# Supply_0.net
KiCad netlist of a schematic drawn in Altium Designer
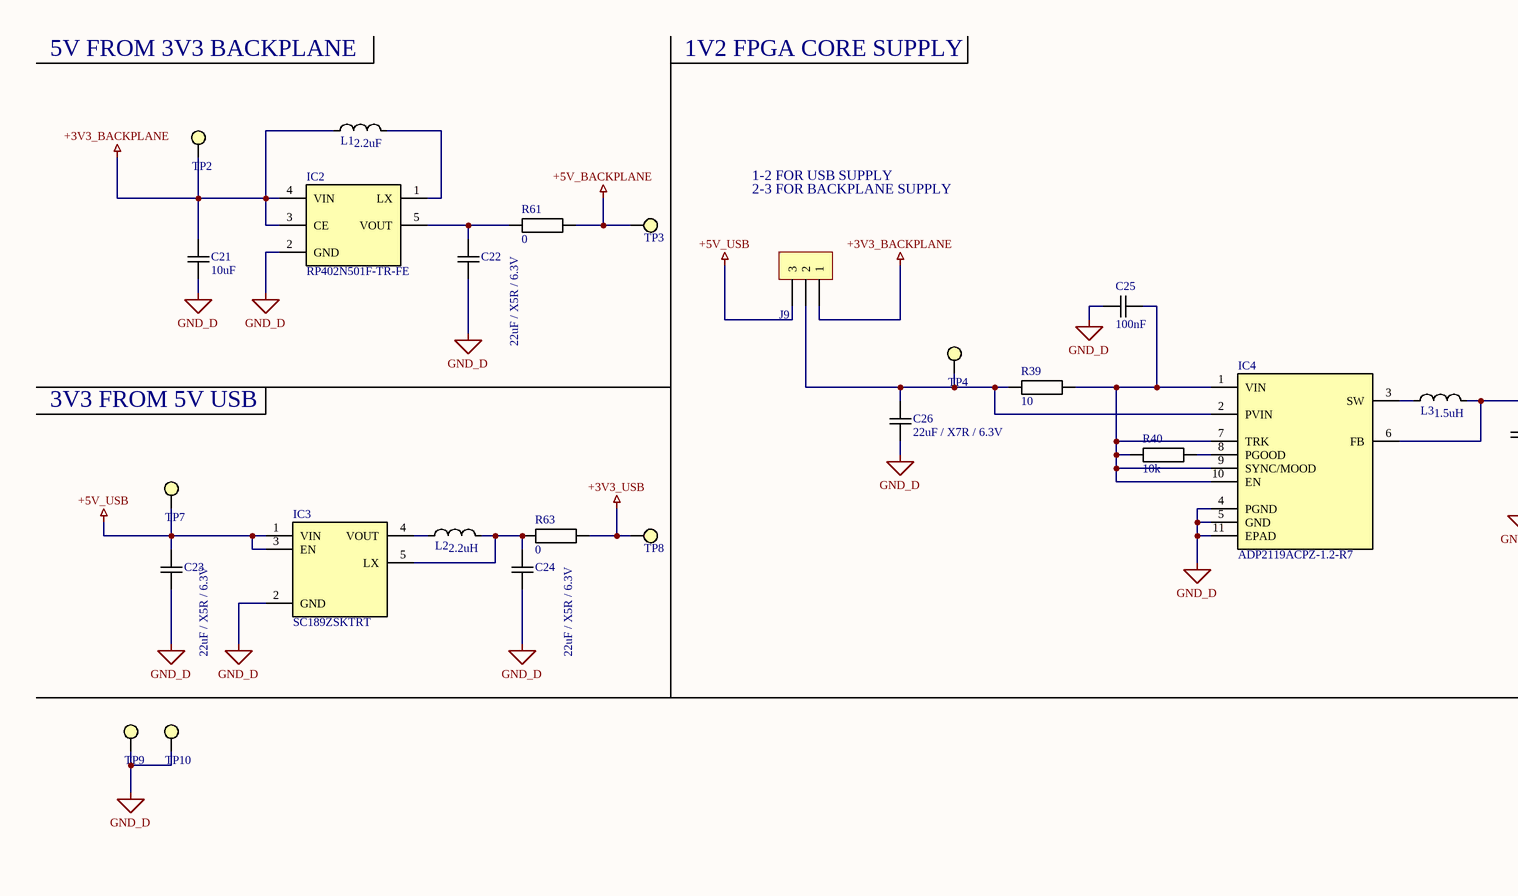
[diagram p0: Supply_0.SchDoc, left]
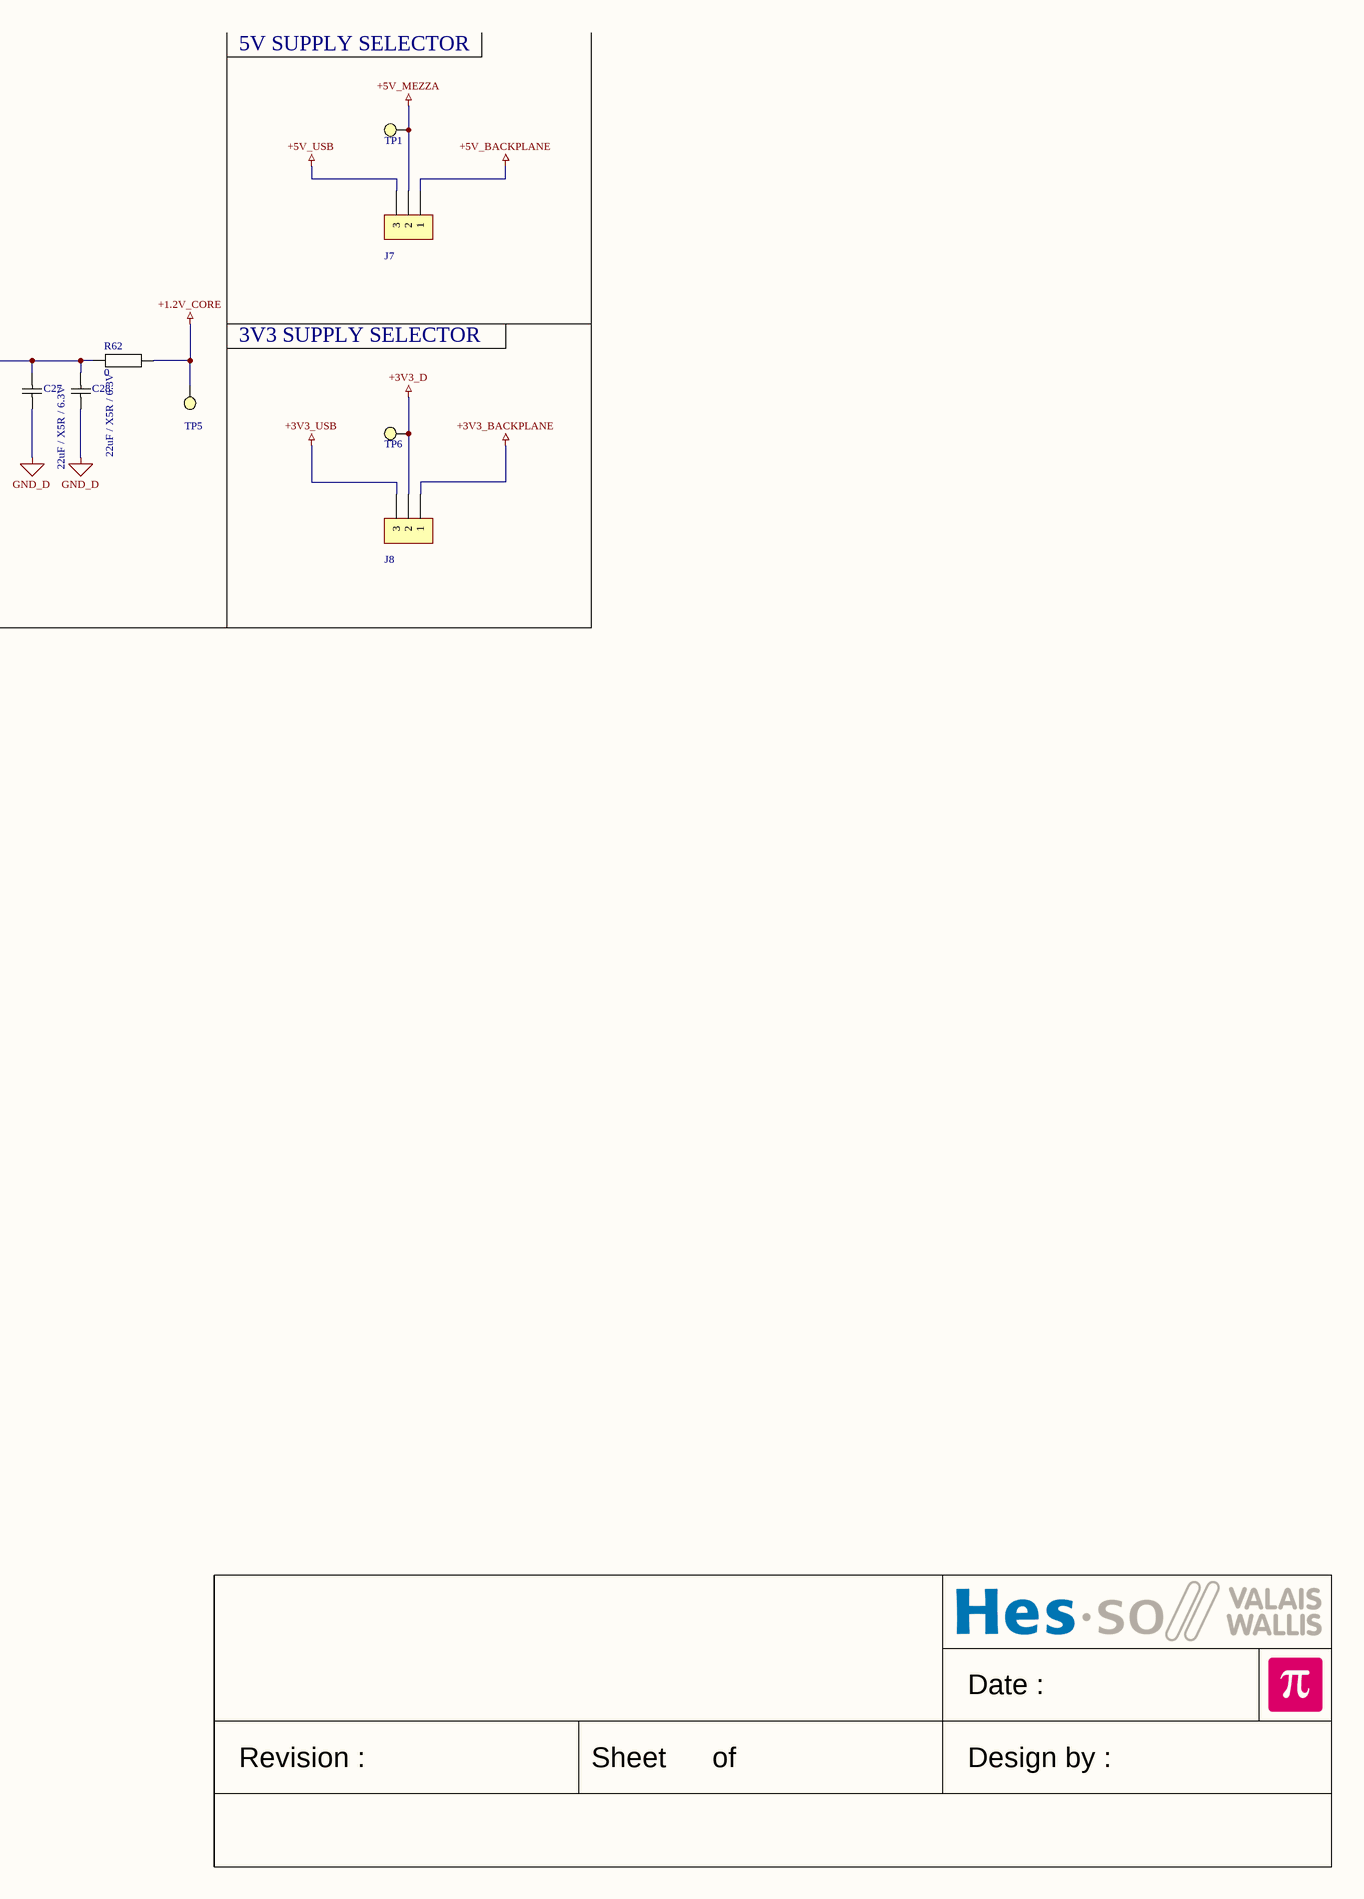
[diagram p1: Supply_0.SchDoc, right]

(export (version "E")
  (design (tool "Eeschema 10.0.6"))
  (components
    (comp (ref "C21")
      (value "10uF")
      (footprint "CAPACITOR 2012 REFLOW")
      (description "Capacitor")
      (libsource (lib "Capacitor") (part "Capacitor"))
    )
    (comp (ref "C22")
      (value "22uF / X5R / 6.3V")
      (footprint "CAPACITOR 2012 REFLOW")
      (description "Capacitor")
      (libsource (lib "Capacitor") (part "Capacitor"))
    )
    (comp (ref "C23")
      (value "22uF / X5R / 6.3V")
      (footprint "CAPACITOR 2012 REFLOW")
      (description "Capacitor")
      (libsource (lib "Capacitor") (part "Capacitor"))
    )
    (comp (ref "C24")
      (value "22uF / X5R / 6.3V")
      (footprint "CAPACITOR 2012 REFLOW")
      (description "Capacitor")
      (libsource (lib "Capacitor") (part "Capacitor"))
    )
    (comp (ref "C25")
      (value "100nF")
      (footprint "CAPACITOR 1608 REFLOW")
      (description "Capacitor")
      (libsource (lib "Capacitor") (part "Capacitor"))
    )
    (comp (ref "C26")
      (value "22uF / X7R / 6.3V")
      (footprint "CAPACITOR 2012 REFLOW")
      (description "Capacitor")
      (libsource (lib "Capacitor") (part "Capacitor"))
    )
    (comp (ref "C27")
      (value "22uF / X5R / 6.3V")
      (footprint "CAPACITOR 2012 REFLOW")
      (description "Capacitor")
      (libsource (lib "Capacitor") (part "Capacitor"))
    )
    (comp (ref "C28")
      (value "22uF / X5R / 6.3V")
      (footprint "CAPACITOR 2012 REFLOW")
      (description "Capacitor")
      (libsource (lib "Capacitor") (part "Capacitor"))
    )
    (comp (ref "IC2")
      (value "RP402N501F-TR-FE")
      (footprint "SamacSys:SOT95P280X130-5N")
      (description "Integrated Circuit")
      (fields (field (name "MOUSER PART NUMBER") "848-RP402N501F-TR-FE"))
      (libsource (lib "SamacSys") (part "RP402N501F-TR-FE"))
    )
    (comp (ref "IC3")
      (value "SC189ZSKTRT")
      (footprint "SamacSys:SOT95P280X145-5N")
      (description "Integrated Circuit")
      (fields (field (name "MOUSER PART NUMBER") "947-SC189ZSKTRT"))
      (libsource (lib "SamacSys") (part "SC189ZSKTRT"))
    )
    (comp (ref "IC4")
      (value "ADP2119ACPZ-1.2-R7")
      (footprint "SamacSys:SON50P300X300X85-11N")
      (description "Integrated Circuit")
      (fields (field (name "MOUSER PART NUMBER") "584-ADP2119ACPZ1.2R7"))
      (libsource (lib "SamacSys") (part "ADP2119ACPZ-1.2-R7"))
    )
    (comp (ref "J7")
      (value "*")
      (footprint "PinHeader1x3 P2.54")
      (description "Plug connector")
      (libsource (lib "PinHeader") (part "PinHeader1x3"))
    )
    (comp (ref "J8")
      (value "*")
      (footprint "PinHeader1x3 P2.54")
      (description "Plug connector")
      (libsource (lib "PinHeader") (part "PinHeader1x3"))
    )
    (comp (ref "J9")
      (value "*")
      (footprint "PinHeader1x3 P2.54")
      (description "Plug connector")
      (libsource (lib "") (part "PinHeader1x3_1"))
    )
    (comp (ref "L1")
      (value "2.2uF")
      (footprint "TDK VLCF5020-1")
      (description "Inductor")
      (libsource (lib "Inductor") (part "Inductor"))
    )
    (comp (ref "L2")
      (value "2.2uH")
      (footprint "TDK VLCF5020-1")
      (description "Inductor")
      (libsource (lib "Inductor") (part "Inductor"))
    )
    (comp (ref "L3")
      (value "1.5uH")
      (footprint "TDK VLCF5020-1")
      (description "Inductor")
      (libsource (lib "Inductor") (part "Inductor"))
    )
    (comp (ref "R39")
      (value "10")
      (footprint "RESISTOR 2012 REFLOW")
      (description "Resistor 1% 50V 125mW 2012(0805)")
      (libsource (lib "Resistor") (part "Resistor"))
    )
    (comp (ref "R40")
      (value "10k")
      (footprint "RESISTOR 1608 REFLOW")
      (description "Resistor 1% 50V 125mW 2012(0805)")
      (libsource (lib "Resistor") (part "Resistor"))
    )
    (comp (ref "R61")
      (value "0")
      (footprint "RESISTOR 1608 REFLOW")
      (description "Resistor 1% 50V 100mW 1608(0603)")
      (libsource (lib "Resistor") (part "Resistor"))
    )
    (comp (ref "R62")
      (value "0")
      (footprint "RESISTOR 1608 REFLOW")
      (description "Resistor 1% 50V 100mW 1608(0603)")
      (libsource (lib "Resistor") (part "Resistor"))
    )
    (comp (ref "R63")
      (value "0")
      (footprint "RESISTOR 1608 REFLOW")
      (description "Resistor 1% 50V 100mW 1608(0603)")
      (libsource (lib "Resistor") (part "Resistor"))
    )
    (comp (ref "TP1")
      (value "*")
      (footprint "Test Point Keystone Miniature RED")
      (description "Test Point")
      (libsource (lib "Testpoint") (part "Test Point"))
    )
    (comp (ref "TP2")
      (value "*")
      (footprint "Test Point Keystone Miniature RED")
      (description "Test Point")
      (libsource (lib "Testpoint") (part "Test Point"))
    )
    (comp (ref "TP3")
      (value "*")
      (footprint "Test Point Keystone Miniature RED")
      (description "Test Point")
      (libsource (lib "Testpoint") (part "Test Point"))
    )
    (comp (ref "TP4")
      (value "*")
      (footprint "Test Point Keystone Miniature RED")
      (description "Test Point")
      (libsource (lib "Testpoint") (part "Test Point"))
    )
    (comp (ref "TP5")
      (value "*")
      (footprint "Test Point Keystone Miniature RED")
      (description "Test Point")
      (libsource (lib "Testpoint") (part "Test Point"))
    )
    (comp (ref "TP6")
      (value "*")
      (footprint "Test Point Keystone Miniature RED")
      (description "Test Point")
      (libsource (lib "Testpoint") (part "Test Point"))
    )
    (comp (ref "TP7")
      (value "*")
      (footprint "Test Point Keystone Miniature RED")
      (description "Test Point")
      (libsource (lib "Testpoint") (part "Test Point"))
    )
    (comp (ref "TP8")
      (value "*")
      (footprint "Test Point Keystone Miniature RED")
      (description "Test Point")
      (libsource (lib "Testpoint") (part "Test Point"))
    )
    (comp (ref "TP9")
      (value "*")
      (footprint "Test Point Keystone Miniature BLACK")
      (description "Test Point")
      (libsource (lib "Testpoint") (part "Test Point"))
    )
    (comp (ref "TP10")
      (value "*")
      (footprint "Test Point Keystone Miniature BLACK")
      (description "Test Point")
      (libsource (lib "Testpoint") (part "Test Point"))
    )
  )
  (nets
    (net (code "1") (name "+1.2V_CORE") (class "Default")
      (node (ref "R62") (pin "2") (pinfunction "2_2") (pintype "passive"))
      (node (ref "TP5") (pin "1") (pinfunction "1_1") (pintype "passive"))
    )
    (net (code "2") (name "+3V3_BACKPLANE") (class "Default")
      (node (ref "C21") (pin "2") (pinfunction "2_2") (pintype "passive"))
      (node (ref "IC2") (pin "3") (pinfunction "CE_3") (pintype "passive"))
      (node (ref "IC2") (pin "4") (pinfunction "VIN_4") (pintype "passive"))
      (node (ref "J8") (pin "1") (pinfunction "1_1") (pintype "passive"))
      (node (ref "J9") (pin "1") (pinfunction "1_1") (pintype "passive"))
      (node (ref "L1") (pin "1") (pinfunction "1_1") (pintype "passive"))
      (node (ref "TP2") (pin "1") (pinfunction "1_1") (pintype "passive"))
    )
    (net (code "3") (name "+3V3_D") (class "Default")
      (node (ref "J8") (pin "2") (pinfunction "2_2") (pintype "passive"))
      (node (ref "TP6") (pin "1") (pinfunction "1_1") (pintype "passive"))
    )
    (net (code "4") (name "+3V3_USB") (class "Default")
      (node (ref "J8") (pin "3") (pinfunction "3_3") (pintype "passive"))
      (node (ref "R63") (pin "2") (pinfunction "2_2") (pintype "passive"))
      (node (ref "TP8") (pin "1") (pinfunction "1_1") (pintype "passive"))
    )
    (net (code "5") (name "+5V_BACKPLANE") (class "Default")
      (node (ref "J7") (pin "1") (pinfunction "1_1") (pintype "passive"))
      (node (ref "R61") (pin "2") (pinfunction "2_2") (pintype "passive"))
      (node (ref "TP3") (pin "1") (pinfunction "1_1") (pintype "passive"))
    )
    (net (code "6") (name "+5V_MEZZA") (class "Default")
      (node (ref "J7") (pin "2") (pinfunction "2_2") (pintype "passive"))
      (node (ref "TP1") (pin "1") (pinfunction "1_1") (pintype "passive"))
    )
    (net (code "7") (name "+5V_USB") (class "Default")
      (node (ref "C23") (pin "2") (pinfunction "2_2") (pintype "passive"))
      (node (ref "IC3") (pin "1") (pinfunction "VIN_1") (pintype "passive"))
      (node (ref "IC3") (pin "3") (pinfunction "EN_3") (pintype "passive"))
      (node (ref "J7") (pin "3") (pinfunction "3_3") (pintype "passive"))
      (node (ref "J9") (pin "3") (pinfunction "3_3") (pintype "passive"))
      (node (ref "TP7") (pin "1") (pinfunction "1_1") (pintype "passive"))
    )
    (net (code "8") (name "GND_D") (class "Default")
      (node (ref "C21") (pin "1") (pinfunction "1_1") (pintype "passive"))
      (node (ref "C22") (pin "1") (pinfunction "1_1") (pintype "passive"))
      (node (ref "C23") (pin "1") (pinfunction "1_1") (pintype "passive"))
      (node (ref "C24") (pin "1") (pinfunction "1_1") (pintype "passive"))
      (node (ref "C25") (pin "2") (pinfunction "2_2") (pintype "passive"))
      (node (ref "C26") (pin "1") (pinfunction "1_1") (pintype "passive"))
      (node (ref "C27") (pin "1") (pinfunction "1_1") (pintype "passive"))
      (node (ref "C28") (pin "1") (pinfunction "1_1") (pintype "passive"))
      (node (ref "IC2") (pin "2") (pinfunction "GND_2") (pintype "passive"))
      (node (ref "IC3") (pin "2") (pinfunction "GND_2") (pintype "passive"))
      (node (ref "IC4") (pin "11") (pinfunction "EPAD_11") (pintype "passive"))
      (node (ref "IC4") (pin "4") (pinfunction "PGND_4") (pintype "passive"))
      (node (ref "IC4") (pin "5") (pinfunction "GND_5") (pintype "passive"))
      (node (ref "TP10") (pin "1") (pinfunction "1_1") (pintype "passive"))
      (node (ref "TP9") (pin "1") (pinfunction "1_1") (pintype "passive"))
    )
    (net (code "9") (name "Net-(IC2-LX)") (class "Default")
      (node (ref "IC2") (pin "1") (pinfunction "LX_1") (pintype "passive"))
      (node (ref "L1") (pin "2") (pinfunction "2_2") (pintype "passive"))
    )
    (net (code "10") (name "Net-(IC2-VOUT)") (class "Default")
      (node (ref "C22") (pin "2") (pinfunction "2_2") (pintype "passive"))
      (node (ref "IC2") (pin "5") (pinfunction "VOUT_5") (pintype "passive"))
      (node (ref "R61") (pin "1") (pinfunction "1_1") (pintype "passive"))
    )
    (net (code "11") (name "Net-(IC3-LX)") (class "Default")
      (node (ref "C24") (pin "2") (pinfunction "2_2") (pintype "passive"))
      (node (ref "IC3") (pin "5") (pinfunction "LX_5") (pintype "passive"))
      (node (ref "L2") (pin "2") (pinfunction "2_2") (pintype "passive"))
      (node (ref "R63") (pin "1") (pinfunction "1_1") (pintype "passive"))
    )
    (net (code "12") (name "Net-(IC3-VOUT)") (class "Default")
      (node (ref "IC3") (pin "4") (pinfunction "VOUT_4") (pintype "passive"))
      (node (ref "L2") (pin "1") (pinfunction "1_1") (pintype "passive"))
    )
    (net (code "13") (name "Net-(IC4-EN)") (class "Default")
      (node (ref "C25") (pin "1") (pinfunction "1_1") (pintype "passive"))
      (node (ref "IC4") (pin "1") (pinfunction "VIN_1") (pintype "passive"))
      (node (ref "IC4") (pin "10") (pinfunction "EN_10") (pintype "passive"))
      (node (ref "IC4") (pin "7") (pinfunction "TRK_7") (pintype "passive"))
      (node (ref "IC4") (pin "9") (pinfunction "SYNC/MOOD_9") (pintype "passive"))
      (node (ref "R39") (pin "1") (pinfunction "1_1") (pintype "passive"))
      (node (ref "R40") (pin "2") (pinfunction "2_2") (pintype "passive"))
    )
    (net (code "14") (name "Net-(IC4-FB)") (class "Default")
      (node (ref "C27") (pin "2") (pinfunction "2_2") (pintype "passive"))
      (node (ref "C28") (pin "2") (pinfunction "2_2") (pintype "passive"))
      (node (ref "IC4") (pin "6") (pinfunction "FB_6") (pintype "passive"))
      (node (ref "L3") (pin "2") (pinfunction "2_2") (pintype "passive"))
      (node (ref "R62") (pin "1") (pinfunction "1_1") (pintype "passive"))
    )
    (net (code "15") (name "Net-(IC4-PGOOD)") (class "Default")
      (node (ref "IC4") (pin "8") (pinfunction "PGOOD_8") (pintype "passive"))
      (node (ref "R40") (pin "1") (pinfunction "1_1") (pintype "passive"))
    )
    (net (code "16") (name "Net-(IC4-PVIN)") (class "Default")
      (node (ref "C26") (pin "2") (pinfunction "2_2") (pintype "passive"))
      (node (ref "IC4") (pin "2") (pinfunction "PVIN_2") (pintype "passive"))
      (node (ref "J9") (pin "2") (pinfunction "2_2") (pintype "passive"))
      (node (ref "R39") (pin "2") (pinfunction "2_2") (pintype "passive"))
      (node (ref "TP4") (pin "1") (pinfunction "1_1") (pintype "passive"))
    )
    (net (code "17") (name "Net-(IC4-SW)") (class "Default")
      (node (ref "IC4") (pin "3") (pinfunction "SW_3") (pintype "passive"))
      (node (ref "L3") (pin "1") (pinfunction "1_1") (pintype "passive"))
    )
  )
)
